# racer.net
KiCad netlist of a schematic drawn in Altium Designer
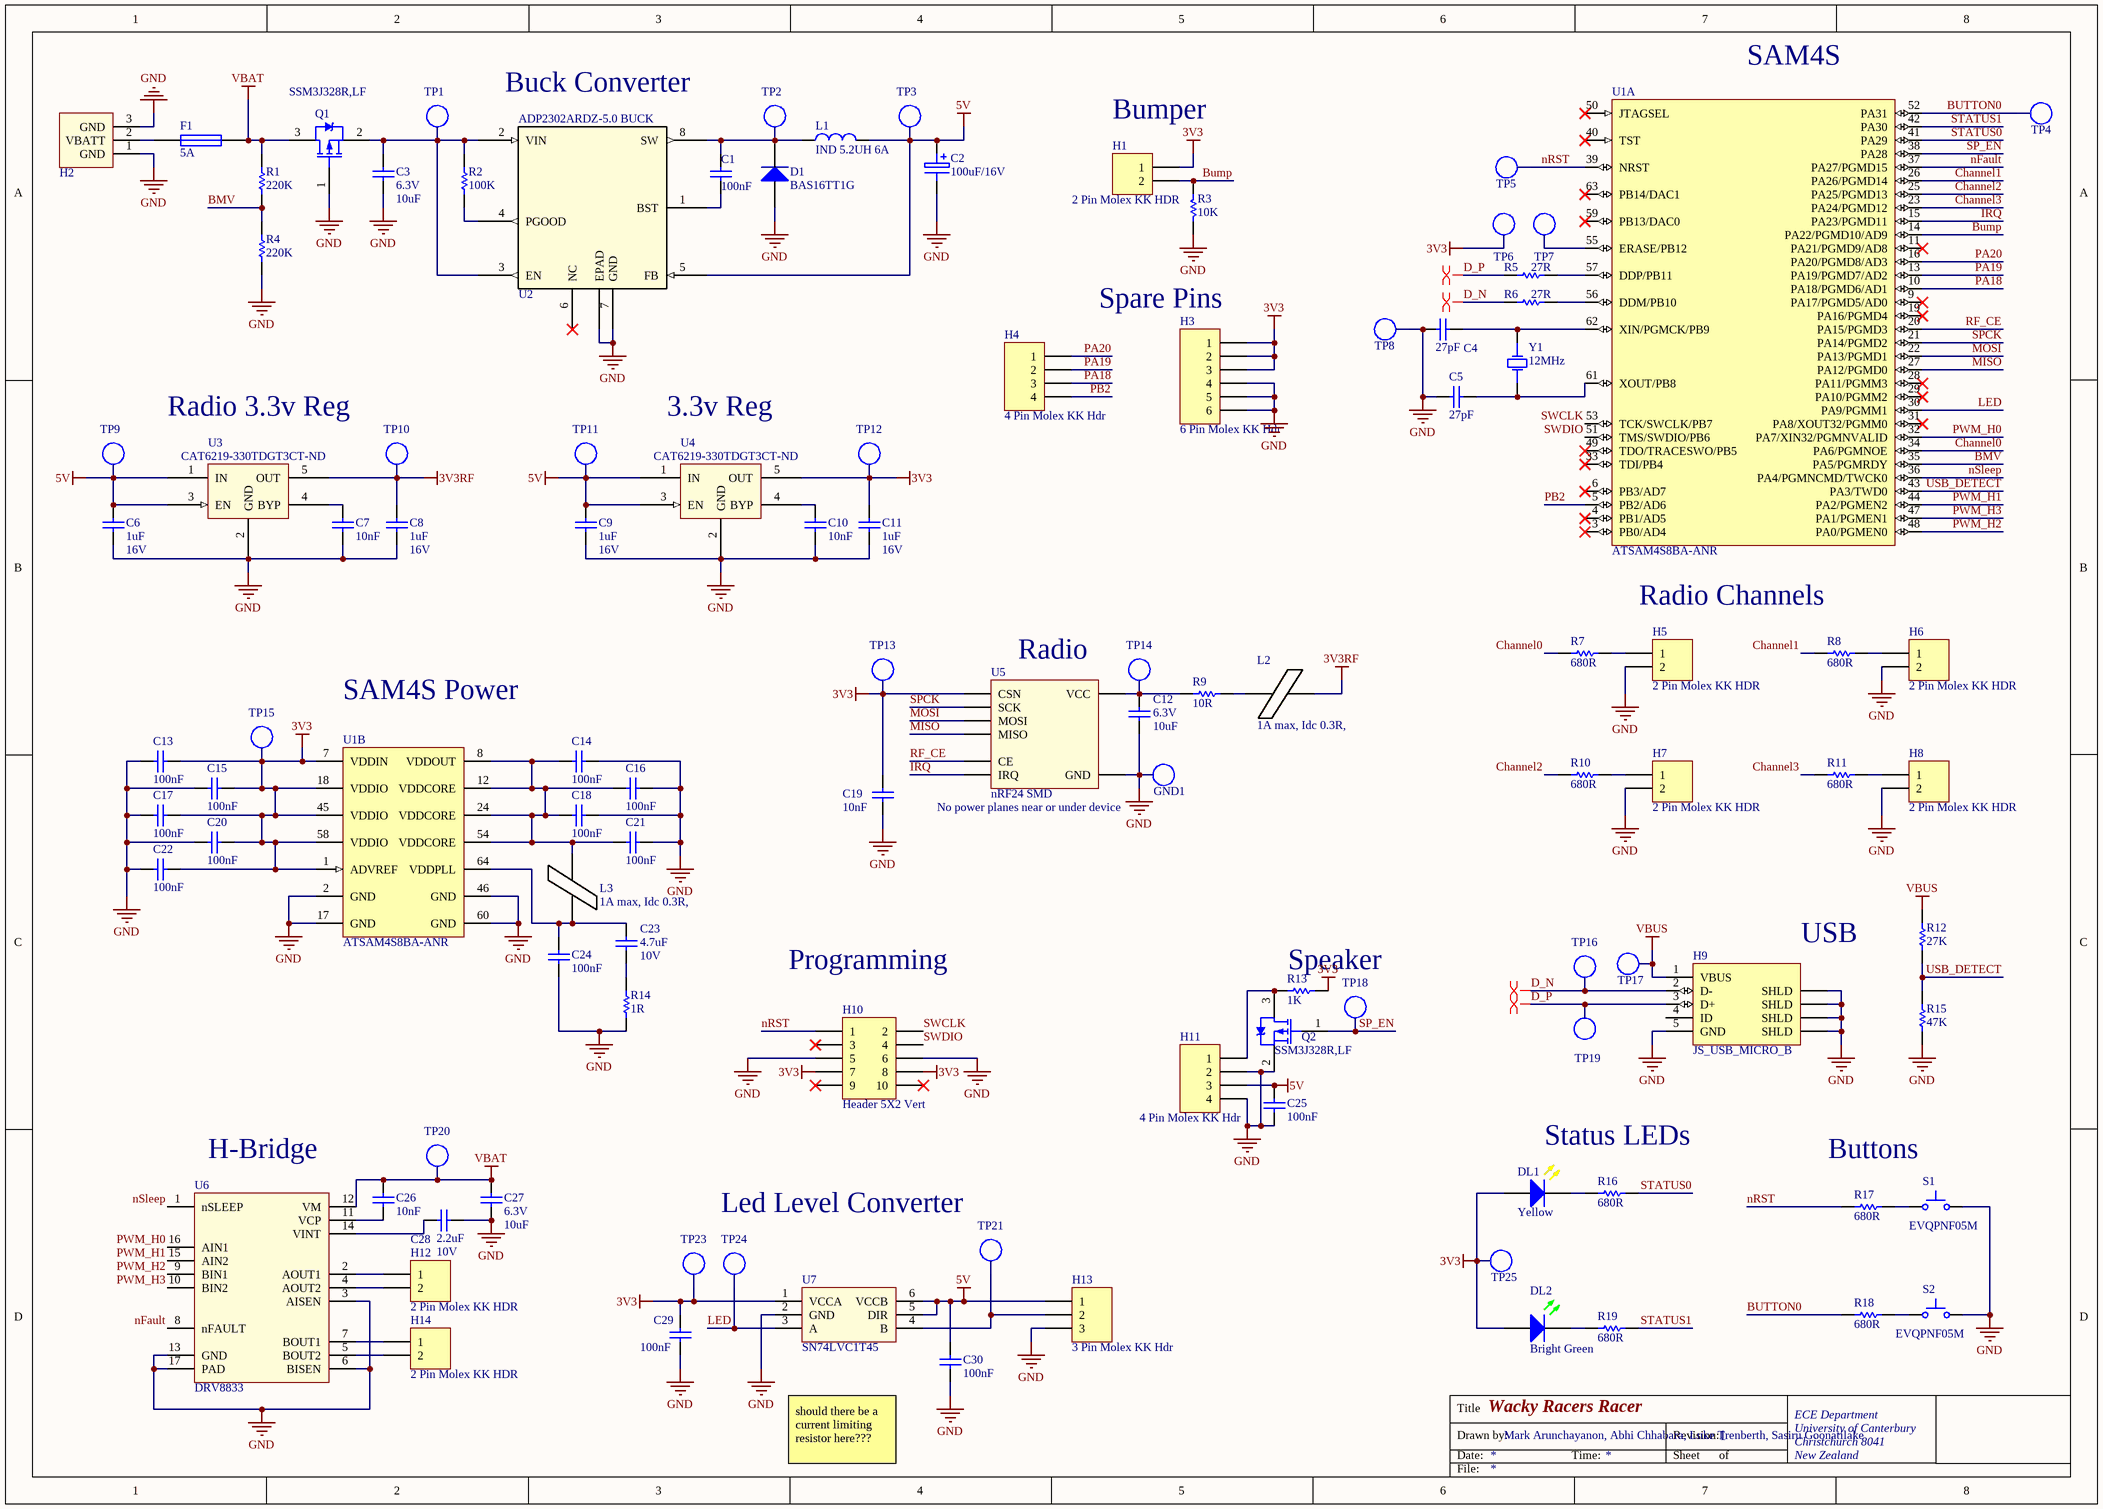
[diagram p0: racer.SchDoc]

(export (version "E")
  (design (tool "Eeschema 10.0.6"))
  (components
    (comp (ref "C1")
      (value "100nF")
      (footprint "CAPC1608L")
      (description "CAP CER 100nF X7R +-10% 50V 0603")
      (libsource (lib "ECE AD19Components_19V1") (part "CC_100nF_0603"))
    )
    (comp (ref "C2")
      (value "100uF/16V")
      (footprint "NICH-1")
      (description "CAP ALUM 100uF 16V SMD")
      (fields (field (name "MANUFACTURER") "Nichcon"))
      (libsource (lib "ECE AD19Components_19V1") (part "CA_100uF_16V"))
    )
    (comp (ref "C3")
      (value "10uF")
      (footprint "CAPC1608L")
      (description "CAP CER 10UF X5R +-20% 6V3 0603")
      (fields (field (name "VOLTAGE - RATED") "6.3V"))
      (libsource (lib "ECE AD19Components_19V1") (part "CC_10uF_0603"))
    )
    (comp (ref "C4")
      (value "27pF")
      (footprint "CAPC1608L")
      (description "CAP CER 27pF NPO/COG +-5% 50V 0603")
      (libsource (lib "ECE AD19Components_19V1") (part "CC_27pF_0603"))
    )
    (comp (ref "C5")
      (value "27pF")
      (footprint "CAPC1608L")
      (description "CAP CER 27pF NPO/COG +-5% 50V 0603")
      (libsource (lib "ECE AD19Components_19V1") (part "CC_27pF_0603"))
    )
    (comp (ref "C6")
      (value "1uF")
      (footprint "CAPC1608L")
      (description "CAP CER 1uF Y5V -20% +80% 16V 0603")
      (fields (field (name "MAX VOLTAGE") "16V"))
      (libsource (lib "ECE AD19Components_19V1") (part "CC_1uF_0603"))
    )
    (comp (ref "C7")
      (value "10nF")
      (footprint "CAPC1608L")
      (description "CAP CER 10nF X7R +-10% 50V 0603")
      (libsource (lib "ECE AD19Components_19V1") (part "CC_10nF_0603"))
    )
    (comp (ref "C8")
      (value "1uF")
      (footprint "CAPC1608L")
      (description "CAP CER 1uF Y5V -20% +80% 16V 0603")
      (fields (field (name "MAX VOLTAGE") "16V"))
      (libsource (lib "ECE AD19Components_19V1") (part "CC_1uF_0603"))
    )
    (comp (ref "C9")
      (value "1uF")
      (footprint "CAPC1608L")
      (description "CAP CER 1uF Y5V -20% +80% 16V 0603")
      (fields (field (name "MAX VOLTAGE") "16V"))
      (libsource (lib "ECE AD19Components_19V1") (part "CC_1uF_0603"))
    )
    (comp (ref "C10")
      (value "10nF")
      (footprint "CAPC1608L")
      (description "CAP CER 10nF X7R +-10% 50V 0603")
      (libsource (lib "ECE AD19Components_19V1") (part "CC_10nF_0603"))
    )
    (comp (ref "C11")
      (value "1uF")
      (footprint "CAPC1608L")
      (description "CAP CER 1uF Y5V -20% +80% 16V 0603")
      (fields (field (name "MAX VOLTAGE") "16V"))
      (libsource (lib "ECE AD19Components_19V1") (part "CC_1uF_0603"))
    )
    (comp (ref "C12")
      (value "10uF")
      (footprint "CAPC1608L")
      (description "CAP CER 10UF X5R +-20% 6V3 0603")
      (fields (field (name "VOLTAGE - RATED") "6.3V"))
      (libsource (lib "ECE AD19Components_19V1") (part "CC_10uF_0603"))
    )
    (comp (ref "C13")
      (value "100nF")
      (footprint "CAPC1608L")
      (description "CAP CER 100nF X7R +-10% 50V 0603")
      (libsource (lib "ECE AD19Components_19V1") (part "CC_100nF_0603"))
    )
    (comp (ref "C14")
      (value "100nF")
      (footprint "CAPC1608L")
      (description "CAP CER 100nF X7R +-10% 50V 0603")
      (libsource (lib "ECE AD19Components_19V1") (part "CC_100nF_0603"))
    )
    (comp (ref "C15")
      (value "100nF")
      (footprint "CAPC1608L")
      (description "CAP CER 100nF X7R +-10% 50V 0603")
      (libsource (lib "ECE AD19Components_19V1") (part "CC_100nF_0603"))
    )
    (comp (ref "C16")
      (value "100nF")
      (footprint "CAPC1608L")
      (description "CAP CER 100nF X7R +-10% 50V 0603")
      (libsource (lib "ECE AD19Components_19V1") (part "CC_100nF_0603"))
    )
    (comp (ref "C17")
      (value "100nF")
      (footprint "CAPC1608L")
      (description "CAP CER 100nF X7R +-10% 50V 0603")
      (libsource (lib "ECE AD19Components_19V1") (part "CC_100nF_0603"))
    )
    (comp (ref "C18")
      (value "100nF")
      (footprint "CAPC1608L")
      (description "CAP CER 100nF X7R +-10% 50V 0603")
      (libsource (lib "ECE AD19Components_19V1") (part "CC_100nF_0603"))
    )
    (comp (ref "C19")
      (value "10nF")
      (footprint "CAPC1608L")
      (description "CAP CER 10nF X7R +-10% 50V 0603")
      (libsource (lib "ECE AD19Components_19V1") (part "CC_10nF_0603"))
    )
    (comp (ref "C20")
      (value "100nF")
      (footprint "CAPC1608L")
      (description "CAP CER 100nF X7R +-10% 50V 0603")
      (libsource (lib "ECE AD19Components_19V1") (part "CC_100nF_0603"))
    )
    (comp (ref "C21")
      (value "100nF")
      (footprint "CAPC1608L")
      (description "CAP CER 100nF X7R +-10% 50V 0603")
      (libsource (lib "ECE AD19Components_19V1") (part "CC_100nF_0603"))
    )
    (comp (ref "C22")
      (value "100nF")
      (footprint "CAPC1608L")
      (description "CAP CER 100nF X7R +-10% 50V 0603")
      (libsource (lib "ECE AD19Components_19V1") (part "CC_100nF_0603"))
    )
    (comp (ref "C23")
      (value "4.7uF")
      (footprint "CAPC1608N")
      (description "CAP CER 4.7uF X5R +-20%  10V 0603")
      (fields (field (name "MAX VOLTAGE") "10V"))
      (libsource (lib "ECE AD19Components_19V1") (part "CC_4.7uF_0603"))
    )
    (comp (ref "C24")
      (value "100nF")
      (footprint "CAPC1608L")
      (description "CAP CER 100nF X7R +-10% 50V 0603")
      (libsource (lib "ECE AD19Components_19V1") (part "CC_100nF_0603"))
    )
    (comp (ref "C25")
      (value "100nF")
      (footprint "CAPC1608L")
      (description "CAP CER 100nF X7R +-10% 50V 0603")
      (libsource (lib "ECE AD19Components_19V1") (part "CC_100nF_0603"))
    )
    (comp (ref "C26")
      (value "10nF")
      (footprint "CAPC1608L")
      (description "CAP CER 10nF X7R +-10% 50V 0603")
      (libsource (lib "ECE AD19Components_19V1") (part "CC_10nF_0603"))
    )
    (comp (ref "C27")
      (value "10uF")
      (footprint "CAPC1608L")
      (description "CAP CER 10UF X5R +-20% 6V3 0603")
      (fields (field (name "VOLTAGE - RATED") "6.3V"))
      (libsource (lib "ECE AD19Components_19V1") (part "CC_10uF_0603"))
    )
    (comp (ref "C28")
      (value "2.2uF")
      (footprint "CAPC1608L")
      (description "CAP CER 2.2uF X5R +-20% 10V 0603")
      (fields (field (name "MAX VOLTAGE") "10V"))
      (libsource (lib "ECE AD19Components_19V1") (part "CC_2.2uF_0603"))
    )
    (comp (ref "C29")
      (value "100nF")
      (footprint "CAPC1608L")
      (description "CAP CER 100nF X7R +-10% 50V 0603")
      (libsource (lib "ECE AD19Components_19V1") (part "CC_100nF_0603"))
    )
    (comp (ref "C30")
      (value "100nF")
      (footprint "CAPC1608L")
      (description "CAP CER 100nF X7R +-10% 50V 0603")
      (libsource (lib "ECE AD19Components_19V1") (part "CC_100nF_0603"))
    )
    (comp (ref "D1")
      (value "BAS16TT1G")
      (footprint "SOT416")
      (description "Diode Switching, Vr 75V, 200mA, SOT-416")
      (fields (field (name "MANUFACTURER") "ON Semiconductor"))
      (libsource (lib "ECE AD19Components_19V1") (part "DR_BAS16TT1G"))
    )
    (comp (ref "DL1")
      (value "Yellow")
      (footprint "WL-SMCW0603")
      (description "LED Yellow 120mcd 0603 SMD")
      (fields
        (field (name "MANUFACTURER") "WURTH ELEKTRONIK")
        (field (name "MANUFACTURER PART NUMBER") "150060YS75000")
        (field (name "LED COLOUR") "Yellow")
      )
      (libsource (lib "ECE AD19Components_19V1") (part "DL_150060YS75000"))
    )
    (comp (ref "DL2")
      (value "Bright Green")
      (footprint "WL-SMCW0603")
      (description "LED Bright Green 40mcd 0603 SMD")
      (fields
        (field (name "MANUFACTURER") "WURTH ELEKTRONIK")
        (field (name "MANUFACTURER PART NUMBER") "150060VS75000")
        (field (name "LED COLOUR") "Bright Green")
      )
      (libsource (lib "ECE AD19Components_19V1") (part "DL_150060VS75000"))
    )
    (comp (ref "F1")
      (value "5A")
      (footprint "RESC3216N")
      (description "Fuse 5.0A Fast Acting 1206 SMD")
      (fields (field (name "MANUFACTURER PART NUMBER") "C1F5") (field (name "MANUFACTURER") "Bel TRP"))
      (libsource (lib "ECE AD19Components_19V1") (part "FS_Fuse_5.0A"))
    )
    (comp (ref "GND1")
      (value "GND")
      (footprint "TP_0603")
      (description "Test Point 1.65X0.9X1.2mm SMD")
      (fields
        (field (name "MANUFACTURER") "TE Connectivity AMP Connectors")
        (field (name "MANUFACTURER PART NUMBER") "1625854-3")
      )
      (libsource (lib "ECE AD19Components_19V1") (part "TP_0603"))
    )
    (comp (ref "H1")
      (value "2 Pin Molex KK HDR")
      (footprint "MOLEX_KK_2_HDR")
      (description "CONN HEADER 2POS 2.54mm VERT_Thru Hole")
      (libsource (lib "") (part "JA_MOLEX_KK_2POS_1"))
    )
    (comp (ref "H2")
      (value "Battery_HEADER_3pin")
      (footprint "BATT_HEADER_3POS")
      (description "3Pin Header 2.54mm spacing")
      (libsource (lib "ENCE461AD19_19V2") (part "Battery_HEADER_3pin"))
    )
    (comp (ref "H3")
      (value "6 Pin Molex KK Hdr")
      (footprint "MOLEX_KK_6_HDR")
      (description "CONN HEADER 6POS 2.54mm VERT_Thru Hole")
      (libsource (lib "ECE AD19Components_19V1") (part "JA_MOLEX_KK_6POS"))
    )
    (comp (ref "H4")
      (value "4 Pin Molex KK Hdr")
      (footprint "MOLEX_KK_4_HDR")
      (description "CONN HEADER 4POS 2.54mm VERT_Thru Hole")
      (fields (field (name "MANUFACTURER") "Molex"))
      (libsource (lib "ECE AD19Components_19V1") (part "JA_MOLEX_KK_4POS"))
    )
    (comp (ref "H5")
      (value "2 Pin Molex KK HDR")
      (footprint "MOLEX_KK_2_HDR")
      (description "CONN HEADER 2POS 2.54mm VERT_Thru Hole")
      (libsource (lib "ECE AD19Components_19V1") (part "JA_MOLEX_KK_2POS"))
    )
    (comp (ref "H6")
      (value "2 Pin Molex KK HDR")
      (footprint "MOLEX_KK_2_HDR")
      (description "CONN HEADER 2POS 2.54mm VERT_Thru Hole")
      (libsource (lib "ECE AD19Components_19V1") (part "JA_MOLEX_KK_2POS"))
    )
    (comp (ref "H7")
      (value "2 Pin Molex KK HDR")
      (footprint "MOLEX_KK_2_HDR")
      (description "CONN HEADER 2POS 2.54mm VERT_Thru Hole")
      (libsource (lib "ECE AD19Components_19V1") (part "JA_MOLEX_KK_2POS"))
    )
    (comp (ref "H8")
      (value "2 Pin Molex KK HDR")
      (footprint "MOLEX_KK_2_HDR")
      (description "CONN HEADER 2POS 2.54mm VERT_Thru Hole")
      (libsource (lib "ECE AD19Components_19V1") (part "JA_MOLEX_KK_2POS"))
    )
    (comp (ref "H9")
      (value "JS_USB_MICRO_B")
      (footprint "FCI_USB_10118194-0001LF")
      (description "CONN USB MICRO B RECPT SMT R/A")
      (fields (field (name "MANUFACTURER") "FCI") (field (name "MANUFACTURER PART NUMBER") "10118194-0001LF"))
      (libsource (lib "CONNECTORS") (part "JS_USB_MICRO_B_SMT"))
    )
    (comp (ref "H10")
      (value "Header 5X2 Vert")
      (footprint "IDC2.54-V10D")
      (description "IDC Header, 2,54mm, 10-Pin, Vert")
      (libsource (lib "ECE AD19Components_19V1") (part "JA_HDR_IDC_5X2_VERT"))
    )
    (comp (ref "H11")
      (value "4 Pin Molex KK Hdr")
      (footprint "MOLEX_KK_4_HDR")
      (description "CONN HEADER 4POS 2.54mm VERT_Thru Hole")
      (fields (field (name "MANUFACTURER") "Molex"))
      (libsource (lib "ECE AD19Components_19V1") (part "JA_MOLEX_KK_4POS"))
    )
    (comp (ref "H12")
      (value "2 Pin Molex KK HDR")
      (footprint "MOLEX_KK_2_HDR")
      (description "CONN HEADER 2POS 2.54mm VERT_Thru Hole")
      (libsource (lib "ECE AD19Components_19V1") (part "JA_MOLEX_KK_2POS"))
    )
    (comp (ref "H13")
      (value "3 Pin Molex KK Hdr")
      (footprint "MOLEX_KK_3_HDR")
      (description "CONN HEADER 3POS 2.54mm VERT_Thru Hole")
      (fields (field (name "MANUFACTURER") "Molex"))
      (libsource (lib "ECE AD19Components_19V1") (part "JA_MOLEX_KK_3POS"))
    )
    (comp (ref "H14")
      (value "2 Pin Molex KK HDR")
      (footprint "MOLEX_KK_2_HDR")
      (description "CONN HEADER 2POS 2.54mm VERT_Thru Hole")
      (libsource (lib "ECE AD19Components_19V1") (part "JA_MOLEX_KK_2POS"))
    )
    (comp (ref "L1")
      (value "IND 5.2UH 6A")
      (footprint "INDUCTOR5u2")
      (description "FIXED IND 5.2UH 6A 22 MOHM SMD")
      (fields
        (field (name "MANUFACTURER") "Sumida America Components Inc.")
        (field (name "MANUFACTURER PART NUMBER") "CDRH104RNP-5R2NC")
      )
      (libsource (lib "ENCE461AD19_19V2") (part "CDRH104RNP-5R2NC"))
    )
    (comp (ref "L2")
      (value "1A max, Idc 0.3R,")
      (footprint "INDC3216L")
      (description "Ferrite Bead, Rdc 0.3R, Z100MHZ 600R, Imax 1A, SMD 1206")
      (fields
        (field (name "MANUFACTURER") "FAIR-RITE")
        (field (name "MANUFACTURER PART NUMBER") "2512066017Y1")
      )
      (libsource (lib "ECE AD19Components_19V1") (part "IN_Ferrite-Bead"))
    )
    (comp (ref "L3")
      (value "1A max, Idc 0.3R,")
      (footprint "INDC3216L")
      (description "Ferrite Bead, Rdc 0.3R, Z100MHZ 600R, Imax 1A, SMD 1206")
      (fields
        (field (name "MANUFACTURER") "FAIR-RITE")
        (field (name "MANUFACTURER PART NUMBER") "2512066017Y1")
      )
      (libsource (lib "ECE AD19Components_19V1") (part "IN_Ferrite-Bead"))
    )
    (comp (ref "Q1")
      (value "SSM3J328R,LF")
      (footprint "SOT23_L")
      (description "MOSFET P-CH 20V 6A SOT23-3")
      (fields
        (field (name "MANUFACTURER") "Toshiba")
        (field (name "MANUFACTURER PART NUMBER") "SSM3J328R,LF")
      )
      (libsource (lib "ECE AD19Components_19V1") (part "TM_SSM3J328R"))
    )
    (comp (ref "Q2")
      (value "SSM3J328R,LF")
      (footprint "SOT23_L")
      (description "MOSFET P-CH 20V 6A SOT23-3")
      (fields
        (field (name "MANUFACTURER") "Toshiba")
        (field (name "MANUFACTURER PART NUMBER") "SSM3J328R,LF")
      )
      (libsource (lib "ECE AD19Components_19V1") (part "TM_SSM3J328R"))
    )
    (comp (ref "R1")
      (value "220K")
      (footprint "RESC1608L")
      (description "RES 3.3K OHM 1/10W 5% 0603 SMD")
      (libsource (lib "ECE AD19Components_19V1") (part "RS_220K"))
    )
    (comp (ref "R2")
      (value "100K")
      (footprint "RESC1608L")
      (description "RES 100K OHM 1/10W 5% 0603 SMD")
      (libsource (lib "ECE AD19Components_19V1") (part "RS_100K"))
    )
    (comp (ref "R3")
      (value "10K")
      (footprint "RESC1608L")
      (description "RES 10.0K OHM 1/10W 5% 0603 SMD")
      (libsource (lib "ECE AD19Components_19V1") (part "RS_10K"))
    )
    (comp (ref "R4")
      (value "220K")
      (footprint "RESC1608L")
      (description "RES 3.3K OHM 1/10W 5% 0603 SMD")
      (libsource (lib "ECE AD19Components_19V1") (part "RS_220K"))
    )
    (comp (ref "R5")
      (value "27R")
      (footprint "RESC3216L")
      (description "RES 27R OHM 1/4W 5% 1206 SMD")
      (libsource (lib "ECE AD19Components_19V1") (part "RT_27R"))
    )
    (comp (ref "R6")
      (value "27R")
      (footprint "RESC3216L")
      (description "RES 27R OHM 1/4W 5% 1206 SMD")
      (libsource (lib "ECE AD19Components_19V1") (part "RT_27R"))
    )
    (comp (ref "R7")
      (value "680R")
      (footprint "RESC1608L")
      (description "RES 680 OHM 1/10W 5% 0603 SMD")
      (libsource (lib "ECE AD19Components_19V1") (part "RS_680R"))
    )
    (comp (ref "R8")
      (value "680R")
      (footprint "RESC1608L")
      (description "RES 680 OHM 1/10W 5% 0603 SMD")
      (libsource (lib "ECE AD19Components_19V1") (part "RS_680R"))
    )
    (comp (ref "R9")
      (value "10R")
      (footprint "RESC1608L")
      (description "RES 10 OHM 1/10W 5% 0603 SMD")
      (libsource (lib "ECE AD19Components_19V1") (part "RS_10R"))
    )
    (comp (ref "R10")
      (value "680R")
      (footprint "RESC1608L")
      (description "RES 680 OHM 1/10W 5% 0603 SMD")
      (libsource (lib "ECE AD19Components_19V1") (part "RS_680R"))
    )
    (comp (ref "R11")
      (value "680R")
      (footprint "RESC1608L")
      (description "RES 680 OHM 1/10W 5% 0603 SMD")
      (libsource (lib "ECE AD19Components_19V1") (part "RS_680R"))
    )
    (comp (ref "R12")
      (value "27K")
      (footprint "RESC1608L")
      (description "RES 27K OHM 1/10W 5% 0603 SMD")
      (libsource (lib "ECE AD19Components_19V1") (part "RS_27K"))
    )
    (comp (ref "R13")
      (value "1K")
      (footprint "RESC1608L")
      (description "RES 1.0K OHM 1/10W 5% 0603 SMD")
      (libsource (lib "ECE AD19Components_19V1") (part "RS_1K"))
    )
    (comp (ref "R14")
      (value "1R")
      (footprint "RESC3216L")
      (description "RES 1R OHM 1/4W 5% 1206 SMD")
      (libsource (lib "ECE AD19Components_19V1") (part "RT_1R"))
    )
    (comp (ref "R15")
      (value "47K")
      (footprint "RESC1608N")
      (description "RES 47.0K OHM 1/10W 5% 0603 SMD")
      (libsource (lib "ECE AD19Components_19V1") (part "RS_47K"))
    )
    (comp (ref "R16")
      (value "680R")
      (footprint "RESC1608L")
      (description "RES 680 OHM 1/10W 5% 0603 SMD")
      (libsource (lib "ECE AD19Components_19V1") (part "RS_680R"))
    )
    (comp (ref "R17")
      (value "680R")
      (footprint "RESC1608L")
      (description "RES 680 OHM 1/10W 5% 0603 SMD")
      (libsource (lib "ECE AD19Components_19V1") (part "RS_680R"))
    )
    (comp (ref "R18")
      (value "680R")
      (footprint "RESC1608L")
      (description "RES 680 OHM 1/10W 5% 0603 SMD")
      (libsource (lib "ECE AD19Components_19V1") (part "RS_680R"))
    )
    (comp (ref "R19")
      (value "680R")
      (footprint "RESC1608L")
      (description "RES 680 OHM 1/10W 5% 0603 SMD")
      (libsource (lib "ECE AD19Components_19V1") (part "RS_680R"))
    )
    (comp (ref "S1")
      (value "EVQPNF05M")
      (footprint "EVQPNF05M")
      (description "Panasonic 6 x 3.5mm SMD Light Touch Switch Type SMD")
      (fields (field (name "MANUFACTURER") "Panasonic"))
      (libsource (lib "ECE AD19Components_19V1") (part "WS_EVQPNF05M"))
    )
    (comp (ref "S2")
      (value "EVQPNF05M")
      (footprint "EVQPNF05M")
      (description "Panasonic 6 x 3.5mm SMD Light Touch Switch Type SMD")
      (fields (field (name "MANUFACTURER") "Panasonic"))
      (libsource (lib "ECE AD19Components_19V1") (part "WS_EVQPNF05M"))
    )
    (comp (ref "TP1")
      (value "VBAT")
      (footprint "TP_0603")
      (description "Test Point 1.65X0.9X1.2mm SMD")
      (fields
        (field (name "MANUFACTURER") "TE Connectivity AMP Connectors")
        (field (name "MANUFACTURER PART NUMBER") "1625854-3")
      )
      (libsource (lib "ECE AD19Components_19V1") (part "TP_0603"))
    )
    (comp (ref "TP2")
      (value "5V")
      (footprint "TP_0603")
      (description "Test Point 1.65X0.9X1.2mm SMD")
      (fields
        (field (name "MANUFACTURER") "TE Connectivity AMP Connectors")
        (field (name "MANUFACTURER PART NUMBER") "1625854-3")
      )
      (libsource (lib "ECE AD19Components_19V1") (part "TP_0603"))
    )
    (comp (ref "TP3")
      (value "5V")
      (footprint "TP_0603")
      (description "Test Point 1.65X0.9X1.2mm SMD")
      (fields
        (field (name "MANUFACTURER") "TE Connectivity AMP Connectors")
        (field (name "MANUFACTURER PART NUMBER") "1625854-3")
      )
      (libsource (lib "ECE AD19Components_19V1") (part "TP_0603"))
    )
    (comp (ref "TP4")
      (value "TP_0603")
      (footprint "TP_0603")
      (description "Test Point 1.65X0.9X1.2mm SMD")
      (fields
        (field (name "MANUFACTURER") "TE Connectivity AMP Connectors")
        (field (name "MANUFACTURER PART NUMBER") "1625854-3")
      )
      (libsource (lib "ECE AD19Components_19V1") (part "TP_0603"))
    )
    (comp (ref "TP5")
      (value "nRST")
      (footprint "TP_0603")
      (description "Test Point 1.65X0.9X1.2mm SMD")
      (fields
        (field (name "MANUFACTURER") "TE Connectivity AMP Connectors")
        (field (name "MANUFACTURER PART NUMBER") "1625854-3")
      )
      (libsource (lib "ECE AD19Components_19V1") (part "TP_0603"))
    )
    (comp (ref "TP6")
      (value "3V3")
      (footprint "TP_0603")
      (description "Test Point 1.65X0.9X1.2mm SMD")
      (fields
        (field (name "MANUFACTURER") "TE Connectivity AMP Connectors")
        (field (name "MANUFACTURER PART NUMBER") "1625854-3")
      )
      (libsource (lib "ECE AD19Components_19V1") (part "TP_0603"))
    )
    (comp (ref "TP7")
      (value "Erase")
      (footprint "TP_0603")
      (description "Test Point 1.65X0.9X1.2mm SMD")
      (fields
        (field (name "MANUFACTURER") "TE Connectivity AMP Connectors")
        (field (name "MANUFACTURER PART NUMBER") "1625854-3")
      )
      (libsource (lib "ECE AD19Components_19V1") (part "TP_0603"))
    )
    (comp (ref "TP8")
      (value "GND")
      (footprint "TP_0603")
      (description "Test Point 1.65X0.9X1.2mm SMD")
      (fields
        (field (name "MANUFACTURER") "TE Connectivity AMP Connectors")
        (field (name "MANUFACTURER PART NUMBER") "1625854-3")
      )
      (libsource (lib "ECE AD19Components_19V1") (part "TP_0603"))
    )
    (comp (ref "TP9")
      (value "5V")
      (footprint "TP_0603")
      (description "Test Point 1.65X0.9X1.2mm SMD")
      (fields
        (field (name "MANUFACTURER") "TE Connectivity AMP Connectors")
        (field (name "MANUFACTURER PART NUMBER") "1625854-3")
      )
      (libsource (lib "ECE AD19Components_19V1") (part "TP_0603"))
    )
    (comp (ref "TP10")
      (value "3V3RF")
      (footprint "TP_0603")
      (description "Test Point 1.65X0.9X1.2mm SMD")
      (fields
        (field (name "MANUFACTURER") "TE Connectivity AMP Connectors")
        (field (name "MANUFACTURER PART NUMBER") "1625854-3")
      )
      (libsource (lib "ECE AD19Components_19V1") (part "TP_0603"))
    )
    (comp (ref "TP11")
      (value "5V")
      (footprint "TP_0603")
      (description "Test Point 1.65X0.9X1.2mm SMD")
      (fields
        (field (name "MANUFACTURER") "TE Connectivity AMP Connectors")
        (field (name "MANUFACTURER PART NUMBER") "1625854-3")
      )
      (libsource (lib "ECE AD19Components_19V1") (part "TP_0603"))
    )
    (comp (ref "TP12")
      (value "3V3")
      (footprint "TP_0603")
      (description "Test Point 1.65X0.9X1.2mm SMD")
      (fields
        (field (name "MANUFACTURER") "TE Connectivity AMP Connectors")
        (field (name "MANUFACTURER PART NUMBER") "1625854-3")
      )
      (libsource (lib "ECE AD19Components_19V1") (part "TP_0603"))
    )
    (comp (ref "TP13")
      (value "3V3")
      (footprint "TP_0603")
      (description "Test Point 1.65X0.9X1.2mm SMD")
      (fields
        (field (name "MANUFACTURER") "TE Connectivity AMP Connectors")
        (field (name "MANUFACTURER PART NUMBER") "1625854-3")
      )
      (libsource (lib "ECE AD19Components_19V1") (part "TP_0603"))
    )
    (comp (ref "TP14")
      (value "3V3RF")
      (footprint "TP_0603")
      (description "Test Point 1.65X0.9X1.2mm SMD")
      (fields
        (field (name "MANUFACTURER") "TE Connectivity AMP Connectors")
        (field (name "MANUFACTURER PART NUMBER") "1625854-3")
      )
      (libsource (lib "ECE AD19Components_19V1") (part "TP_0603"))
    )
    (comp (ref "TP15")
      (value "3V3")
      (footprint "TP_0603")
      (description "Test Point 1.65X0.9X1.2mm SMD")
      (fields
        (field (name "MANUFACTURER") "TE Connectivity AMP Connectors")
        (field (name "MANUFACTURER PART NUMBER") "1625854-3")
      )
      (libsource (lib "ECE AD19Components_19V1") (part "TP_0603"))
    )
    (comp (ref "TP16")
      (value "D_N")
      (footprint "TP_0603")
      (description "Test Point 1.65X0.9X1.2mm SMD")
      (fields
        (field (name "MANUFACTURER") "TE Connectivity AMP Connectors")
        (field (name "MANUFACTURER PART NUMBER") "1625854-3")
      )
      (libsource (lib "ECE AD19Components_19V1") (part "TP_0603"))
    )
    (comp (ref "TP17")
      (value "VBUS")
      (footprint "TP_0603")
      (description "Test Point 1.65X0.9X1.2mm SMD")
      (fields
        (field (name "MANUFACTURER") "TE Connectivity AMP Connectors")
        (field (name "MANUFACTURER PART NUMBER") "1625854-3")
      )
      (libsource (lib "ECE AD19Components_19V1") (part "TP_0603"))
    )
    (comp (ref "TP18")
      (value "SP_EN")
      (footprint "TP_0603")
      (description "Test Point 1.65X0.9X1.2mm SMD")
      (fields
        (field (name "MANUFACTURER") "TE Connectivity AMP Connectors")
        (field (name "MANUFACTURER PART NUMBER") "1625854-3")
      )
      (libsource (lib "ECE AD19Components_19V1") (part "TP_0603"))
    )
    (comp (ref "TP19")
      (value "D_P")
      (footprint "TP_0603")
      (description "Test Point 1.65X0.9X1.2mm SMD")
      (fields
        (field (name "MANUFACTURER") "TE Connectivity AMP Connectors")
        (field (name "MANUFACTURER PART NUMBER") "1625854-3")
      )
      (libsource (lib "ECE AD19Components_19V1") (part "TP_0603"))
    )
    (comp (ref "TP20")
      (value "VBAT")
      (footprint "TP_0603")
      (description "Test Point 1.65X0.9X1.2mm SMD")
      (fields
        (field (name "MANUFACTURER") "TE Connectivity AMP Connectors")
        (field (name "MANUFACTURER PART NUMBER") "1625854-3")
      )
      (libsource (lib "ECE AD19Components_19V1") (part "TP_0603"))
    )
    (comp (ref "TP21")
      (value "LEDB")
      (footprint "TP_0603")
      (description "Test Point 1.65X0.9X1.2mm SMD")
      (fields
        (field (name "MANUFACTURER") "TE Connectivity AMP Connectors")
        (field (name "MANUFACTURER PART NUMBER") "1625854-3")
      )
      (libsource (lib "ECE AD19Components_19V1") (part "TP_0603"))
    )
    (comp (ref "TP23")
      (value "3V3")
      (footprint "TP_0603")
      (description "Test Point 1.65X0.9X1.2mm SMD")
      (fields
        (field (name "MANUFACTURER") "TE Connectivity AMP Connectors")
        (field (name "MANUFACTURER PART NUMBER") "1625854-3")
      )
      (libsource (lib "ECE AD19Components_19V1") (part "TP_0603"))
    )
    (comp (ref "TP24")
      (value "LEDA")
      (footprint "TP_0603")
      (description "Test Point 1.65X0.9X1.2mm SMD")
      (fields
        (field (name "MANUFACTURER") "TE Connectivity AMP Connectors")
        (field (name "MANUFACTURER PART NUMBER") "1625854-3")
      )
      (libsource (lib "ECE AD19Components_19V1") (part "TP_0603"))
    )
    (comp (ref "TP25")
      (value "3V3")
      (footprint "TP_0603")
      (description "Test Point 1.65X0.9X1.2mm SMD")
      (fields
        (field (name "MANUFACTURER") "TE Connectivity AMP Connectors")
        (field (name "MANUFACTURER PART NUMBER") "1625854-3")
      )
      (libsource (lib "ECE AD19Components_19V1") (part "TP_0603"))
    )
    (comp (ref "U1")
      (value "ATSAM4S8BA-ANR")
      (footprint "LQFP64_L")
      (description "IC MCU 32BIT 512KB FLASH 64LQFP")
      (fields (field (name "MANUFACTURER") "Atmel"))
      (libsource (lib "ECE AD19Components_19V1") (part "SE_ATSAM4S16BA-MU"))
    )
    (comp (ref "U2")
      (value "ADP2302ARDZ-5.0 BUCK")
      (footprint "RD_8_1")
      (description "IC REG BUCK 5V 2A 8SOIC")
      (fields (field (name "MANUFACTURER_PART_NUMBER") "ADP2302ARDZ-5.0-R7"))
      (libsource (lib "ENCE461AD19_19V2") (part "ADP2302ARDZ-5.0-R7"))
    )
    (comp (ref "U3")
      (value "CAT6219-330TDGT3")
      (footprint "SOT95P280X145-5N")
      (description "IC REG LIN 3.3V 500MA TSOT23-5")
      (fields
        (field (name "BASE PART NUMBER") "CAT6219")
        (field (name "SUPPLIER PART NUMBER") "CAT6219-330TDGT3CT-ND")
      )
      (libsource (lib "ENCE461AD19_19V2") (part "SV_CAT6219-330TDGT3"))
    )
    (comp (ref "U4")
      (value "CAT6219-330TDGT3")
      (footprint "SOT95P280X145-5N")
      (description "IC REG LIN 3.3V 500MA TSOT23-5")
      (fields
        (field (name "BASE PART NUMBER") "CAT6219")
        (field (name "SUPPLIER PART NUMBER") "CAT6219-330TDGT3CT-ND")
      )
      (libsource (lib "ENCE461AD19_19V2") (part "SV_CAT6219-330TDGT3"))
    )
    (comp (ref "U5")
      (value "nRF24 SMD")
      (footprint "NRF24")
      (description "nRF24 SMD Module")
      (fields (field (name "WARNING") "No power planes near or under device"))
      (libsource (lib "ENCE461AD19_19V2") (part "NRF24"))
    )
    (comp (ref "U6")
      (value "DRV8833")
      (footprint "HTSOP16")
      (description "Dual H-Bridge Motor Driver 1.5A")
      (libsource (lib "ENCE461AD19_19V2") (part "DRV8833"))
    )
    (comp (ref "U7")
      (value "SN74LVC1T45")
      (footprint "SOT23-6_N")
      (description "1.8V - 5V level converter")
      (libsource (lib "ENCE461_extras_2020") (part "SN74LVC1T45"))
    )
    (comp (ref "Y1")
      (value "12MHz")
      (footprint "6.0X3.5-4")
      (description "CRYSTAL 12MHZ 18PF 6X3.5mm SMD")
      (fields
        (field (name "MANUFACTURER") "CTS-Frequency Controls")
        (field (name "MANUFACTURER PART NUMBER") "406C35D12M00000")
        (field (name "FREQUENCY") "12MHz")
      )
      (libsource (lib "ECE AD19Components_19V1") (part "XT_CRYSTAL_12MHz_18pF"))
    )
  )
  (nets
    (net (code "1") (name "/BMV") (class "Default")
      (node (ref "R1") (pin "1") (pinfunction "1_1") (pintype "passive"))
      (node (ref "R4") (pin "2") (pinfunction "2_2") (pintype "passive"))
      (node (ref "U1") (pin "35") (pinfunction "PA5/PGMRDY_35") (pintype "bidirectional"))
    )
    (net (code "2") (name "/BUTTON0") (class "Default")
      (node (ref "R18") (pin "1") (pinfunction "1_1") (pintype "passive"))
      (node (ref "TP4") (pin "1") (pinfunction "TP_1") (pintype "passive"))
      (node (ref "U1") (pin "52") (pinfunction "PA31_52") (pintype "bidirectional"))
    )
    (net (code "3") (name "/Bump") (class "Default")
      (node (ref "H1") (pin "2") (pinfunction "2_2") (pintype "passive"))
      (node (ref "R3") (pin "2") (pinfunction "2_2") (pintype "passive"))
      (node (ref "U1") (pin "14") (pinfunction "PA22/PGMD10/AD9_14") (pintype "bidirectional"))
    )
    (net (code "4") (name "/Channel0") (class "Default")
      (node (ref "R7") (pin "1") (pinfunction "1_1") (pintype "passive"))
      (node (ref "U1") (pin "34") (pinfunction "PA6/PGMNOE_34") (pintype "bidirectional"))
    )
    (net (code "5") (name "/Channel1") (class "Default")
      (node (ref "R8") (pin "1") (pinfunction "1_1") (pintype "passive"))
      (node (ref "U1") (pin "26") (pinfunction "PA26/PGMD14_26") (pintype "bidirectional"))
    )
    (net (code "6") (name "/Channel2") (class "Default")
      (node (ref "R10") (pin "1") (pinfunction "1_1") (pintype "passive"))
      (node (ref "U1") (pin "25") (pinfunction "PA25/PGMD13_25") (pintype "bidirectional"))
    )
    (net (code "7") (name "/Channel3") (class "Default")
      (node (ref "R11") (pin "1") (pinfunction "1_1") (pintype "passive"))
      (node (ref "U1") (pin "23") (pinfunction "PA24/PGMD12_23") (pintype "bidirectional"))
    )
    (net (code "8") (name "/D_N") (class "Default")
      (node (ref "H9") (pin "2") (pinfunction "D-_2") (pintype "bidirectional"))
      (node (ref "R6") (pin "1") (pinfunction "1_1") (pintype "passive"))
      (node (ref "TP16") (pin "1") (pinfunction "TP_1") (pintype "passive"))
    )
    (net (code "9") (name "/D_P") (class "Default")
      (node (ref "H9") (pin "3") (pinfunction "D+_3") (pintype "bidirectional"))
      (node (ref "R5") (pin "1") (pinfunction "1_1") (pintype "passive"))
      (node (ref "TP19") (pin "1") (pinfunction "TP_1") (pintype "passive"))
    )
    (net (code "10") (name "/IRQ") (class "Default")
      (node (ref "U1") (pin "15") (pinfunction "PA23/PGMD11_15") (pintype "bidirectional"))
      (node (ref "U5") (pin "8") (pinfunction "IRQ_8") (pintype "passive"))
    )
    (net (code "11") (name "/LED") (class "Default")
      (node (ref "TP24") (pin "1") (pinfunction "TP_1") (pintype "passive"))
      (node (ref "U1") (pin "30") (pinfunction "PA9/PGMM1_30") (pintype "bidirectional"))
      (node (ref "U7") (pin "3") (pinfunction "A_3") (pintype "passive"))
    )
    (net (code "12") (name "/MISO") (class "Default")
      (node (ref "U1") (pin "27") (pinfunction "PA12/PGMD0_27") (pintype "bidirectional"))
      (node (ref "U5") (pin "7") (pinfunction "MISO_7") (pintype "passive"))
    )
    (net (code "13") (name "/MOSI") (class "Default")
      (node (ref "U1") (pin "22") (pinfunction "PA13/PGMD1_22") (pintype "bidirectional"))
      (node (ref "U5") (pin "6") (pinfunction "MOSI_6") (pintype "passive"))
    )
    (net (code "14") (name "/PA18") (class "Default")
      (node (ref "H4") (pin "3") (pinfunction "3_3") (pintype "passive"))
      (node (ref "U1") (pin "10") (pinfunction "PA18/PGMD6/AD1_10") (pintype "bidirectional"))
    )
    (net (code "15") (name "/PA19") (class "Default")
      (node (ref "H4") (pin "2") (pinfunction "2_2") (pintype "passive"))
      (node (ref "U1") (pin "13") (pinfunction "PA19/PGMD7/AD2_13") (pintype "bidirectional"))
    )
    (net (code "16") (name "/PA20") (class "Default")
      (node (ref "H4") (pin "1") (pinfunction "1_1") (pintype "passive"))
      (node (ref "U1") (pin "16") (pinfunction "PA20/PGMD8/AD3_16") (pintype "bidirectional"))
    )
    (net (code "17") (name "/PB2") (class "Default")
      (node (ref "H4") (pin "4") (pinfunction "4_4") (pintype "passive"))
      (node (ref "U1") (pin "5") (pinfunction "PB2/AD6_5") (pintype "bidirectional"))
    )
    (net (code "18") (name "/PWM_H0") (class "Default")
      (node (ref "U1") (pin "32") (pinfunction "PA7/XIN32/PGMNVALID_32") (pintype "bidirectional"))
      (node (ref "U6") (pin "16") (pinfunction "AIN1_16") (pintype "passive"))
    )
    (net (code "19") (name "/PWM_H1") (class "Default")
      (node (ref "U1") (pin "44") (pinfunction "PA2/PGMEN2_44") (pintype "bidirectional"))
      (node (ref "U6") (pin "15") (pinfunction "AIN2_15") (pintype "passive"))
    )
    (net (code "20") (name "/PWM_H2") (class "Default")
      (node (ref "U1") (pin "48") (pinfunction "PA0/PGMEN0_48") (pintype "bidirectional"))
      (node (ref "U6") (pin "9") (pinfunction "BIN1_9") (pintype "passive"))
    )
    (net (code "21") (name "/PWM_H3") (class "Default")
      (node (ref "U1") (pin "47") (pinfunction "PA1/PGMEN1_47") (pintype "bidirectional"))
      (node (ref "U6") (pin "10") (pinfunction "BIN2_10") (pintype "passive"))
    )
    (net (code "22") (name "/RF_CE") (class "Default")
      (node (ref "U1") (pin "20") (pinfunction "PA15/PGMD3_20") (pintype "bidirectional"))
      (node (ref "U5") (pin "3") (pinfunction "CE_3") (pintype "passive"))
    )
    (net (code "23") (name "/SPCK") (class "Default")
      (node (ref "U1") (pin "21") (pinfunction "PA14/PGMD2_21") (pintype "bidirectional"))
      (node (ref "U5") (pin "5") (pinfunction "SCK_5") (pintype "passive"))
    )
    (net (code "24") (name "/SP_EN") (class "Default")
      (node (ref "Q2") (pin "1") (pinfunction "1_1") (pintype "passive"))
      (node (ref "TP18") (pin "1") (pinfunction "TP_1") (pintype "passive"))
      (node (ref "U1") (pin "38") (pinfunction "PA28_38") (pintype "bidirectional"))
    )
    (net (code "25") (name "/STATUS0") (class "Default")
      (node (ref "R16") (pin "2") (pinfunction "2_2") (pintype "passive"))
      (node (ref "U1") (pin "41") (pinfunction "PA29_41") (pintype "bidirectional"))
    )
    (net (code "26") (name "/STATUS1") (class "Default")
      (node (ref "R19") (pin "2") (pinfunction "2_2") (pintype "passive"))
      (node (ref "U1") (pin "42") (pinfunction "PA30_42") (pintype "bidirectional"))
    )
    (net (code "27") (name "/SWCLK") (class "Default")
      (node (ref "H10") (pin "2") (pinfunction "2_2") (pintype "passive"))
      (node (ref "U1") (pin "53") (pinfunction "TCK/SWCLK/PB7_53") (pintype "bidirectional"))
    )
    (net (code "28") (name "/SWDIO") (class "Default")
      (node (ref "H10") (pin "4") (pinfunction "4_4") (pintype "passive"))
      (node (ref "U1") (pin "51") (pinfunction "TMS/SWDIO/PB6_51") (pintype "bidirectional"))
    )
    (net (code "29") (name "/USB_DETECT") (class "Default")
      (node (ref "R12") (pin "1") (pinfunction "1_1") (pintype "passive"))
      (node (ref "R15") (pin "2") (pinfunction "2_2") (pintype "passive"))
      (node (ref "U1") (pin "43") (pinfunction "PA3/TWD0_43") (pintype "bidirectional"))
    )
    (net (code "30") (name "/nFault") (class "Default")
      (node (ref "U1") (pin "37") (pinfunction "PA27/PGMD15_37") (pintype "bidirectional"))
      (node (ref "U6") (pin "8") (pinfunction "nFAULT_8") (pintype "passive"))
    )
    (net (code "31") (name "/nRST") (class "Default")
      (node (ref "H10") (pin "1") (pinfunction "1_1") (pintype "passive"))
      (node (ref "R17") (pin "1") (pinfunction "1_1") (pintype "passive"))
      (node (ref "TP5") (pin "1") (pinfunction "TP_1") (pintype "passive"))
      (node (ref "U1") (pin "39") (pinfunction "NRST_39") (pintype "bidirectional"))
    )
    (net (code "32") (name "/nSleep") (class "Default")
      (node (ref "U1") (pin "36") (pinfunction "PA4/PGMNCMD/TWCK0_36") (pintype "bidirectional"))
      (node (ref "U6") (pin "1") (pinfunction "nSLEEP_1") (pintype "passive"))
    )
    (net (code "33") (name "3V3") (class "Default")
      (node (ref "C11") (pin "2") (pinfunction "2_2") (pintype "passive"))
      (node (ref "C13") (pin "1") (pinfunction "1_1") (pintype "passive"))
      (node (ref "C15") (pin "1") (pinfunction "1_1") (pintype "passive"))
      (node (ref "C17") (pin "1") (pinfunction "1_1") (pintype "passive"))
      (node (ref "C19") (pin "2") (pinfunction "2_2") (pintype "passive"))
      (node (ref "C20") (pin "1") (pinfunction "1_1") (pintype "passive"))
      (node (ref "C22") (pin "1") (pinfunction "1_1") (pintype "passive"))
      (node (ref "C29") (pin "1") (pinfunction "1_1") (pintype "passive"))
      (node (ref "DL1") (pin "2") (pinfunction "A_2") (pintype "passive"))
      (node (ref "DL2") (pin "2") (pinfunction "A_2") (pintype "passive"))
      (node (ref "H1") (pin "1") (pinfunction "1_1") (pintype "passive"))
      (node (ref "H10") (pin "7") (pinfunction "7_7") (pintype "passive"))
      (node (ref "H10") (pin "8") (pinfunction "8_8") (pintype "passive"))
      (node (ref "H3") (pin "1") (pinfunction "1_1") (pintype "passive"))
      (node (ref "H3") (pin "2") (pinfunction "2_2") (pintype "passive"))
      (node (ref "H3") (pin "3") (pinfunction "3_3") (pintype "passive"))
      (node (ref "R13") (pin "2") (pinfunction "2_2") (pintype "passive"))
      (node (ref "TP12") (pin "1") (pinfunction "TP_1") (pintype "passive"))
      (node (ref "TP13") (pin "1") (pinfunction "TP_1") (pintype "passive"))
      (node (ref "TP15") (pin "1") (pinfunction "TP_1") (pintype "passive"))
      (node (ref "TP23") (pin "1") (pinfunction "TP_1") (pintype "passive"))
      (node (ref "TP25") (pin "1") (pinfunction "TP_1") (pintype "passive"))
      (node (ref "TP6") (pin "1") (pinfunction "TP_1") (pintype "passive"))
      (node (ref "U1") (pin "1") (pinfunction "ADVREF_1") (pintype "input"))
      (node (ref "U1") (pin "18") (pinfunction "VDDIO_18") (pintype "power_in"))
      (node (ref "U1") (pin "45") (pinfunction "VDDIO_45") (pintype "power_in"))
      (node (ref "U1") (pin "58") (pinfunction "VDDIO_58") (pintype "power_in"))
      (node (ref "U1") (pin "7") (pinfunction "VDDIN_7") (pintype "power_in"))
      (node (ref "U4") (pin "5") (pinfunction "OUT_5") (pintype "power_in"))
      (node (ref "U5") (pin "4") (pinfunction "CSN_4") (pintype "passive"))
      (node (ref "U7") (pin "1") (pinfunction "VCCA_1") (pintype "passive"))
    )
    (net (code "34") (name "3V3RF") (class "Default")
      (node (ref "C8") (pin "2") (pinfunction "2_2") (pintype "passive"))
      (node (ref "L2") (pin "2") (pinfunction "2_2") (pintype "passive"))
      (node (ref "TP10") (pin "1") (pinfunction "TP_1") (pintype "passive"))
      (node (ref "U3") (pin "5") (pinfunction "OUT_5") (pintype "power_in"))
    )
    (net (code "35") (name "5V") (class "Default")
      (node (ref "C2") (pin "2") (pintype "passive"))
      (node (ref "C25") (pin "2") (pinfunction "2_2") (pintype "passive"))
      (node (ref "C30") (pin "1") (pinfunction "1_1") (pintype "passive"))
      (node (ref "C6") (pin "2") (pinfunction "2_2") (pintype "passive"))
      (node (ref "C9") (pin "2") (pinfunction "2_2") (pintype "passive"))
      (node (ref "H11") (pin "3") (pinfunction "3_3") (pintype "passive"))
      (node (ref "H13") (pin "1") (pinfunction "1_1") (pintype "passive"))
      (node (ref "L1") (pin "2") (pintype "passive"))
      (node (ref "TP11") (pin "1") (pinfunction "TP_1") (pintype "passive"))
      (node (ref "TP3") (pin "1") (pinfunction "TP_1") (pintype "passive"))
      (node (ref "TP9") (pin "1") (pinfunction "TP_1") (pintype "passive"))
      (node (ref "U2") (pin "5") (pinfunction "FB_5") (pintype "input"))
      (node (ref "U3") (pin "1") (pinfunction "IN_1") (pintype "power_in"))
      (node (ref "U3") (pin "3") (pinfunction "EN_3") (pintype "input"))
      (node (ref "U4") (pin "1") (pinfunction "IN_1") (pintype "power_in"))
      (node (ref "U4") (pin "3") (pinfunction "EN_3") (pintype "input"))
      (node (ref "U7") (pin "5") (pinfunction "DIR_5") (pintype "passive"))
      (node (ref "U7") (pin "6") (pinfunction "VCCB_6") (pintype "passive"))
    )
    (net (code "36") (name "GND") (class "Default")
      (node (ref "C10") (pin "1") (pinfunction "1_1") (pintype "passive"))
      (node (ref "C11") (pin "1") (pinfunction "1_1") (pintype "passive"))
      (node (ref "C12") (pin "1") (pinfunction "1_1") (pintype "passive"))
      (node (ref "C13") (pin "2") (pinfunction "2_2") (pintype "passive"))
      (node (ref "C14") (pin "1") (pinfunction "1_1") (pintype "passive"))
      (node (ref "C15") (pin "2") (pinfunction "2_2") (pintype "passive"))
      (node (ref "C16") (pin "1") (pinfunction "1_1") (pintype "passive"))
      (node (ref "C17") (pin "2") (pinfunction "2_2") (pintype "passive"))
      (node (ref "C18") (pin "1") (pinfunction "1_1") (pintype "passive"))
      (node (ref "C19") (pin "1") (pinfunction "1_1") (pintype "passive"))
      (node (ref "C2") (pin "1") (pintype "passive"))
      (node (ref "C20") (pin "2") (pinfunction "2_2") (pintype "passive"))
      (node (ref "C21") (pin "1") (pinfunction "1_1") (pintype "passive"))
      (node (ref "C22") (pin "2") (pinfunction "2_2") (pintype "passive"))
      (node (ref "C24") (pin "2") (pinfunction "2_2") (pintype "passive"))
      (node (ref "C25") (pin "1") (pinfunction "1_1") (pintype "passive"))
      (node (ref "C27") (pin "1") (pinfunction "1_1") (pintype "passive"))
      (node (ref "C28") (pin "2") (pinfunction "2_2") (pintype "passive"))
      (node (ref "C29") (pin "2") (pinfunction "2_2") (pintype "passive"))
      (node (ref "C3") (pin "1") (pinfunction "1_1") (pintype "passive"))
      (node (ref "C30") (pin "2") (pinfunction "2_2") (pintype "passive"))
      (node (ref "C4") (pin "2") (pinfunction "2_2") (pintype "passive"))
      (node (ref "C5") (pin "2") (pinfunction "2_2") (pintype "passive"))
      (node (ref "C6") (pin "1") (pinfunction "1_1") (pintype "passive"))
      (node (ref "C7") (pin "1") (pinfunction "1_1") (pintype "passive"))
      (node (ref "C8") (pin "1") (pinfunction "1_1") (pintype "passive"))
      (node (ref "C9") (pin "1") (pinfunction "1_1") (pintype "passive"))
      (node (ref "D1") (pin "1") (pinfunction "A_1") (pintype "passive"))
      (node (ref "GND1") (pin "1") (pinfunction "TP_1") (pintype "passive"))
      (node (ref "H10") (pin "5") (pinfunction "5_5") (pintype "passive"))
      (node (ref "H10") (pin "6") (pinfunction "6_6") (pintype "passive"))
      (node (ref "H11") (pin "2") (pinfunction "2_2") (pintype "passive"))
      (node (ref "H11") (pin "4") (pinfunction "4_4") (pintype "passive"))
      (node (ref "H13") (pin "3") (pinfunction "3_3") (pintype "passive"))
      (node (ref "H2") (pin "1") (pinfunction "GND_1") (pintype "passive"))
      (node (ref "H2") (pin "3") (pinfunction "GND_3") (pintype "passive"))
      (node (ref "H3") (pin "4") (pinfunction "4_4") (pintype "passive"))
      (node (ref "H3") (pin "5") (pinfunction "5_5") (pintype "passive"))
      (node (ref "H3") (pin "6") (pinfunction "6_6") (pintype "passive"))
      (node (ref "H5") (pin "2") (pinfunction "2_2") (pintype "passive"))
      (node (ref "H6") (pin "2") (pinfunction "2_2") (pintype "passive"))
      (node (ref "H7") (pin "2") (pinfunction "2_2") (pintype "passive"))
      (node (ref "H8") (pin "2") (pinfunction "2_2") (pintype "passive"))
      (node (ref "H9") (pin "5") (pinfunction "GND_5") (pintype "passive"))
      (node (ref "H9") (pin "6") (pinfunction "SHLD_6") (pintype "passive"))
      (node (ref "Q1") (pin "1") (pinfunction "1_1") (pintype "passive"))
      (node (ref "Q2") (pin "2") (pinfunction "2_2") (pintype "passive"))
      (node (ref "R14") (pin "1") (pinfunction "1_1") (pintype "passive"))
      (node (ref "R15") (pin "1") (pinfunction "1_1") (pintype "passive"))
      (node (ref "R3") (pin "1") (pinfunction "1_1") (pintype "passive"))
      (node (ref "R4") (pin "1") (pinfunction "1_1") (pintype "passive"))
      (node (ref "S1") (pin "2") (pintype "passive"))
      (node (ref "S2") (pin "2") (pintype "passive"))
      (node (ref "TP8") (pin "1") (pinfunction "TP_1") (pintype "passive"))
      (node (ref "U1") (pin "17") (pinfunction "GND_17") (pintype "power_in"))
      (node (ref "U1") (pin "2") (pinfunction "GND_2") (pintype "power_in"))
      (node (ref "U1") (pin "46") (pinfunction "GND_46") (pintype "power_in"))
      (node (ref "U1") (pin "60") (pinfunction "GND_60") (pintype "power_in"))
      (node (ref "U2") (pin "7") (pinfunction "GND_7") (pintype "power_in"))
      (node (ref "U2") (pin "EPAD") (pinfunction "EPAD_EPAD") (pintype "passive"))
      (node (ref "U3") (pin "2") (pinfunction "GND_2") (pintype "power_in"))
      (node (ref "U4") (pin "2") (pinfunction "GND_2") (pintype "power_in"))
      (node (ref "U5") (pin "2") (pinfunction "GND_2") (pintype "passive"))
      (node (ref "U6") (pin "13") (pinfunction "GND_13") (pintype "passive"))
      (node (ref "U6") (pin "17") (pinfunction "PAD_17") (pintype "passive"))
      (node (ref "U6") (pin "3") (pinfunction "AISEN_3") (pintype "passive"))
      (node (ref "U6") (pin "6") (pinfunction "BISEN_6") (pintype "passive"))
      (node (ref "U7") (pin "2") (pinfunction "GND_2") (pintype "passive"))
    )
    (net (code "37") (name "Net-(C23-Pad1)") (class "Default")
      (node (ref "C23") (pin "1") (pinfunction "1_1") (pintype "passive"))
      (node (ref "R14") (pin "2") (pinfunction "2_2") (pintype "passive"))
    )
    (net (code "38") (name "Net-(D1-K)") (class "Default")
      (node (ref "C1") (pin "1") (pinfunction "1_1") (pintype "passive"))
      (node (ref "D1") (pin "3") (pinfunction "K_3") (pintype "passive"))
      (node (ref "L1") (pin "1") (pintype "passive"))
      (node (ref "TP2") (pin "1") (pinfunction "TP_1") (pintype "passive"))
      (node (ref "U2") (pin "8") (pinfunction "SW_8") (pintype "output"))
    )
    (net (code "39") (name "Net-(DL1-K)") (class "Default")
      (node (ref "DL1") (pin "1") (pinfunction "K_1") (pintype "passive"))
      (node (ref "R16") (pin "1") (pinfunction "1_1") (pintype "passive"))
    )
    (net (code "40") (name "Net-(DL2-K)") (class "Default")
      (node (ref "DL2") (pin "1") (pinfunction "K_1") (pintype "passive"))
      (node (ref "R19") (pin "1") (pinfunction "1_1") (pintype "passive"))
    )
    (net (code "41") (name "Net-(H2-VBATT)") (class "Default")
      (node (ref "F1") (pin "1") (pinfunction "1_1") (pintype "passive"))
      (node (ref "H2") (pin "2") (pinfunction "VBATT_2") (pintype "passive"))
    )
    (net (code "42") (name "Net-(H5-Pad1)") (class "Default")
      (node (ref "H5") (pin "1") (pinfunction "1_1") (pintype "passive"))
      (node (ref "R7") (pin "2") (pinfunction "2_2") (pintype "passive"))
    )
    (net (code "43") (name "Net-(H6-Pad1)") (class "Default")
      (node (ref "H6") (pin "1") (pinfunction "1_1") (pintype "passive"))
      (node (ref "R8") (pin "2") (pinfunction "2_2") (pintype "passive"))
    )
    (net (code "44") (name "Net-(H7-Pad1)") (class "Default")
      (node (ref "H7") (pin "1") (pinfunction "1_1") (pintype "passive"))
      (node (ref "R10") (pin "2") (pinfunction "2_2") (pintype "passive"))
    )
    (net (code "45") (name "Net-(H8-Pad1)") (class "Default")
      (node (ref "H8") (pin "1") (pinfunction "1_1") (pintype "passive"))
      (node (ref "R11") (pin "2") (pinfunction "2_2") (pintype "passive"))
    )
    (net (code "46") (name "Net-(H11-Pad1)") (class "Default")
      (node (ref "H11") (pin "1") (pinfunction "1_1") (pintype "passive"))
      (node (ref "Q2") (pin "3") (pinfunction "3_3") (pintype "passive"))
      (node (ref "R13") (pin "1") (pinfunction "1_1") (pintype "passive"))
    )
    (net (code "47") (name "Net-(L2-Pad1)") (class "Default")
      (node (ref "L2") (pin "1") (pinfunction "1_1") (pintype "passive"))
      (node (ref "R9") (pin "2") (pinfunction "2_2") (pintype "passive"))
    )
    (net (code "48") (name "Net-(R17-Pad2)") (class "Default")
      (node (ref "R17") (pin "2") (pinfunction "2_2") (pintype "passive"))
      (node (ref "S1") (pin "1") (pintype "passive"))
    )
    (net (code "49") (name "Net-(R18-Pad2)") (class "Default")
      (node (ref "R18") (pin "2") (pinfunction "2_2") (pintype "passive"))
      (node (ref "S2") (pin "1") (pintype "passive"))
    )
    (net (code "50") (name "Net-(TP1-TP)") (class "Default")
      (node (ref "C3") (pin "2") (pinfunction "2_2") (pintype "passive"))
      (node (ref "Q1") (pin "2") (pinfunction "2_2") (pintype "passive"))
      (node (ref "R2") (pin "2") (pinfunction "2_2") (pintype "passive"))
      (node (ref "TP1") (pin "1") (pinfunction "TP_1") (pintype "passive"))
      (node (ref "U2") (pin "2") (pinfunction "VIN_2") (pintype "input"))
      (node (ref "U2") (pin "3") (pinfunction "EN_3") (pintype "output"))
    )
    (net (code "51") (name "Net-(TP7-TP)") (class "Default")
      (node (ref "TP7") (pin "1") (pinfunction "TP_1") (pintype "passive"))
      (node (ref "U1") (pin "55") (pinfunction "ERASE/PB12_55") (pintype "bidirectional"))
    )
    (net (code "52") (name "Net-(TP14-TP)") (class "Default")
      (node (ref "C12") (pin "2") (pinfunction "2_2") (pintype "passive"))
      (node (ref "R9") (pin "1") (pinfunction "1_1") (pintype "passive"))
      (node (ref "TP14") (pin "1") (pinfunction "TP_1") (pintype "passive"))
      (node (ref "U5") (pin "1") (pinfunction "VCC_1") (pintype "passive"))
    )
    (net (code "53") (name "Net-(TP21-TP)") (class "Default")
      (node (ref "H13") (pin "2") (pinfunction "2_2") (pintype "passive"))
      (node (ref "TP21") (pin "1") (pinfunction "TP_1") (pintype "passive"))
      (node (ref "U7") (pin "4") (pinfunction "B_4") (pintype "passive"))
    )
    (net (code "54") (name "Net-(U1A-DDM{slash}PB10)") (class "Default")
      (node (ref "R6") (pin "2") (pinfunction "2_2") (pintype "passive"))
      (node (ref "U1") (pin "56") (pinfunction "DDM/PB10_56") (pintype "bidirectional"))
    )
    (net (code "55") (name "Net-(U1A-DDP{slash}PB11)") (class "Default")
      (node (ref "R5") (pin "2") (pinfunction "2_2") (pintype "passive"))
      (node (ref "U1") (pin "57") (pinfunction "DDP/PB11_57") (pintype "bidirectional"))
    )
    (net (code "56") (name "Net-(U1A-XIN{slash}PGMCK{slash}PB9)") (class "Default")
      (node (ref "C4") (pin "1") (pinfunction "1_1") (pintype "passive"))
      (node (ref "U1") (pin "62") (pinfunction "XIN/PGMCK/PB9_62") (pintype "bidirectional"))
      (node (ref "Y1") (pin "3") (pinfunction "OSC2_3") (pintype "passive"))
    )
    (net (code "57") (name "Net-(U1A-XOUT{slash}PB8)") (class "Default")
      (node (ref "C5") (pin "1") (pinfunction "1_1") (pintype "passive"))
      (node (ref "U1") (pin "61") (pinfunction "XOUT/PB8_61") (pintype "bidirectional"))
      (node (ref "Y1") (pin "1") (pinfunction "OSC1_1") (pintype "passive"))
    )
    (net (code "58") (name "Net-(U1B-VDDOUT)") (class "Default")
      (node (ref "C14") (pin "2") (pinfunction "2_2") (pintype "passive"))
      (node (ref "C16") (pin "2") (pinfunction "2_2") (pintype "passive"))
      (node (ref "C18") (pin "2") (pinfunction "2_2") (pintype "passive"))
      (node (ref "C21") (pin "2") (pinfunction "2_2") (pintype "passive"))
      (node (ref "L3") (pin "2") (pinfunction "2_2") (pintype "passive"))
      (node (ref "U1") (pin "12") (pinfunction "VDDCORE_12") (pintype "power_in"))
      (node (ref "U1") (pin "24") (pinfunction "VDDCORE_24") (pintype "power_in"))
      (node (ref "U1") (pin "54") (pinfunction "VDDCORE_54") (pintype "power_in"))
      (node (ref "U1") (pin "8") (pinfunction "VDDOUT_8") (pintype "power_in"))
    )
    (net (code "59") (name "Net-(U1B-VDDPLL)") (class "Default")
      (node (ref "C23") (pin "2") (pinfunction "2_2") (pintype "passive"))
      (node (ref "C24") (pin "1") (pinfunction "1_1") (pintype "passive"))
      (node (ref "L3") (pin "1") (pinfunction "1_1") (pintype "passive"))
      (node (ref "U1") (pin "64") (pinfunction "VDDPLL_64") (pintype "power_in"))
    )
    (net (code "60") (name "Net-(U2-BST)") (class "Default")
      (node (ref "C1") (pin "2") (pinfunction "2_2") (pintype "passive"))
      (node (ref "U2") (pin "1") (pinfunction "BST_1") (pintype "passive"))
    )
    (net (code "61") (name "Net-(U2-PGOOD)") (class "Default")
      (node (ref "R2") (pin "1") (pinfunction "1_1") (pintype "passive"))
      (node (ref "U2") (pin "4") (pinfunction "PGOOD_4") (pintype "output"))
    )
    (net (code "62") (name "Net-(U3-BYP)") (class "Default")
      (node (ref "C7") (pin "2") (pinfunction "2_2") (pintype "passive"))
      (node (ref "U3") (pin "4") (pinfunction "BYP_4") (pintype "passive"))
    )
    (net (code "63") (name "Net-(U4-BYP)") (class "Default")
      (node (ref "C10") (pin "2") (pinfunction "2_2") (pintype "passive"))
      (node (ref "U4") (pin "4") (pinfunction "BYP_4") (pintype "passive"))
    )
    (net (code "64") (name "Net-(U6-AOUT1)") (class "Default")
      (node (ref "H12") (pin "1") (pinfunction "1_1") (pintype "passive"))
      (node (ref "U6") (pin "2") (pinfunction "AOUT1_2") (pintype "passive"))
    )
    (net (code "65") (name "Net-(U6-AOUT2)") (class "Default")
      (node (ref "H12") (pin "2") (pinfunction "2_2") (pintype "passive"))
      (node (ref "U6") (pin "4") (pinfunction "AOUT2_4") (pintype "passive"))
    )
    (net (code "66") (name "Net-(U6-BOUT1)") (class "Default")
      (node (ref "H14") (pin "1") (pinfunction "1_1") (pintype "passive"))
      (node (ref "U6") (pin "7") (pinfunction "BOUT1_7") (pintype "passive"))
    )
    (net (code "67") (name "Net-(U6-BOUT2)") (class "Default")
      (node (ref "H14") (pin "2") (pinfunction "2_2") (pintype "passive"))
      (node (ref "U6") (pin "5") (pinfunction "BOUT2_5") (pintype "passive"))
    )
    (net (code "68") (name "Net-(U6-VCP)") (class "Default")
      (node (ref "C26") (pin "2") (pinfunction "2_2") (pintype "passive"))
      (node (ref "U6") (pin "11") (pinfunction "VCP_11") (pintype "passive"))
    )
    (net (code "69") (name "Net-(U6-VINT)") (class "Default")
      (node (ref "C28") (pin "1") (pinfunction "1_1") (pintype "passive"))
      (node (ref "U6") (pin "14") (pinfunction "VINT_14") (pintype "passive"))
    )
    (net (code "70") (name "VBAT") (class "Default")
      (node (ref "C26") (pin "1") (pinfunction "1_1") (pintype "passive"))
      (node (ref "C27") (pin "2") (pinfunction "2_2") (pintype "passive"))
      (node (ref "F1") (pin "2") (pinfunction "2_2") (pintype "passive"))
      (node (ref "Q1") (pin "3") (pinfunction "3_3") (pintype "passive"))
      (node (ref "R1") (pin "2") (pinfunction "2_2") (pintype "passive"))
      (node (ref "TP20") (pin "1") (pinfunction "TP_1") (pintype "passive"))
      (node (ref "U6") (pin "12") (pinfunction "VM_12") (pintype "passive"))
    )
    (net (code "71") (name "VBUS") (class "Default")
      (node (ref "H9") (pin "1") (pinfunction "VBUS_1") (pintype "power_in"))
      (node (ref "R12") (pin "2") (pinfunction "2_2") (pintype "passive"))
      (node (ref "TP17") (pin "1") (pinfunction "TP_1") (pintype "passive"))
    )
    (net (code "72") (name "unconnected-(H9-ID-Pad4)") (class "Default")
      (node (ref "H9") (pin "4") (pinfunction "ID_4") (pintype "power_in"))
    )
    (net (code "73") (name "unconnected-(H10-Pad3)") (class "Default")
      (node (ref "H10") (pin "3") (pinfunction "3_3") (pintype "passive+no_connect"))
    )
    (net (code "74") (name "unconnected-(H10-Pad9)") (class "Default")
      (node (ref "H10") (pin "9") (pinfunction "9_9") (pintype "passive+no_connect"))
    )
    (net (code "75") (name "unconnected-(H10-Pad10)") (class "Default")
      (node (ref "H10") (pin "10") (pinfunction "10_10") (pintype "passive+no_connect"))
    )
    (net (code "76") (name "unconnected-(U1A-JTAGSEL-Pad50)") (class "Default")
      (node (ref "U1") (pin "50") (pinfunction "JTAGSEL_50") (pintype "input+no_connect"))
    )
    (net (code "77") (name "unconnected-(U1A-PA8{slash}XOUT32{slash}PGMM0-Pad31)") (class "Default")
      (node (ref "U1") (pin "31") (pinfunction "PA8/XOUT32/PGMM0_31") (pintype "bidirectional+no_connect"))
    )
    (net (code "78") (name "unconnected-(U1A-PA10{slash}PGMM2-Pad29)") (class "Default")
      (node (ref "U1") (pin "29") (pinfunction "PA10/PGMM2_29") (pintype "bidirectional+no_connect"))
    )
    (net (code "79") (name "unconnected-(U1A-PA11{slash}PGMM3-Pad28)") (class "Default")
      (node (ref "U1") (pin "28") (pinfunction "PA11/PGMM3_28") (pintype "bidirectional+no_connect"))
    )
    (net (code "80") (name "unconnected-(U1A-PA16{slash}PGMD4-Pad19)") (class "Default")
      (node (ref "U1") (pin "19") (pinfunction "PA16/PGMD4_19") (pintype "bidirectional+no_connect"))
    )
    (net (code "81") (name "unconnected-(U1A-PA17{slash}PGMD5{slash}AD0-Pad9)") (class "Default")
      (node (ref "U1") (pin "9") (pinfunction "PA17/PGMD5/AD0_9") (pintype "bidirectional+no_connect"))
    )
    (net (code "82") (name "unconnected-(U1A-PA21{slash}PGMD9{slash}AD8-Pad11)") (class "Default")
      (node (ref "U1") (pin "11") (pinfunction "PA21/PGMD9/AD8_11") (pintype "bidirectional+no_connect"))
    )
    (net (code "83") (name "unconnected-(U1A-PB0{slash}AD4-Pad3)") (class "Default")
      (node (ref "U1") (pin "3") (pinfunction "PB0/AD4_3") (pintype "bidirectional+no_connect"))
    )
    (net (code "84") (name "unconnected-(U1A-PB1{slash}AD5-Pad4)") (class "Default")
      (node (ref "U1") (pin "4") (pinfunction "PB1/AD5_4") (pintype "bidirectional+no_connect"))
    )
    (net (code "85") (name "unconnected-(U1A-PB3{slash}AD7-Pad6)") (class "Default")
      (node (ref "U1") (pin "6") (pinfunction "PB3/AD7_6") (pintype "bidirectional+no_connect"))
    )
    (net (code "86") (name "unconnected-(U1A-PB13{slash}DAC0-Pad59)") (class "Default")
      (node (ref "U1") (pin "59") (pinfunction "PB13/DAC0_59") (pintype "bidirectional+no_connect"))
    )
    (net (code "87") (name "unconnected-(U1A-PB14{slash}DAC1-Pad63)") (class "Default")
      (node (ref "U1") (pin "63") (pinfunction "PB14/DAC1_63") (pintype "bidirectional+no_connect"))
    )
    (net (code "88") (name "unconnected-(U1A-TDI{slash}PB4-Pad33)") (class "Default")
      (node (ref "U1") (pin "33") (pinfunction "TDI/PB4_33") (pintype "bidirectional+no_connect"))
    )
    (net (code "89") (name "unconnected-(U1A-TDO{slash}TRACESWO{slash}PB5-Pad49)") (class "Default")
      (node (ref "U1") (pin "49") (pinfunction "TDO/TRACESWO/PB5_49") (pintype "bidirectional+no_connect"))
    )
    (net (code "90") (name "unconnected-(U1A-TST-Pad40)") (class "Default")
      (node (ref "U1") (pin "40") (pinfunction "TST_40") (pintype "input+no_connect"))
    )
    (net (code "91") (name "unconnected-(U2-NC-Pad6)") (class "Default")
      (node (ref "U2") (pin "6") (pinfunction "NC_6") (pintype "passive+no_connect"))
    )
  )
)
